# SHIELD1_1.net
KiCad netlist of a schematic drawn in EAGLE
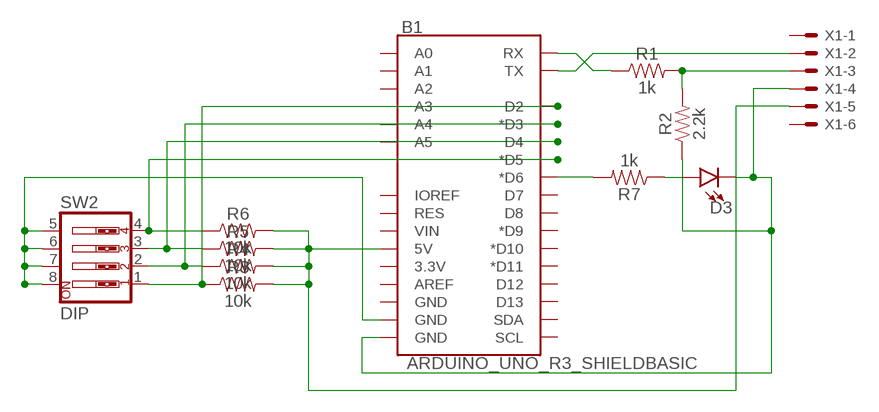
[diagram p0: schematic, sheet 1]

(export (version "E")
  (design (tool "Eeschema 10.0.6"))
  (components
    (comp (ref "B1")
      (value "ARDUINO_UNO_R3_SHIELDBASIC")
      (footprint "eagle-import:UNO_R3_SHIELD")
      (libsource (lib "eagle-import") (part "ARDUINO_UNO_R3_SHIELDBASIC"))
    )
    (comp (ref "D3")
      (value "LED5MM")
      (footprint "eagle-import:LED_5MM")
      (libsource (lib "eagle-import") (part "LED5MM"))
    )
    (comp (ref "R1")
      (value "1k")
      (footprint "eagle-import:AXIAL-0.3")
      (libsource (lib "eagle-import") (part "1KOHM-HORIZ-1/4W-1%"))
    )
    (comp (ref "R2")
      (value "2.2k")
      (footprint "eagle-import:AXIAL-0.3")
      (libsource (lib "eagle-import") (part "1KOHM-HORIZ-1/4W-1%"))
    )
    (comp (ref "R3")
      (value "10k")
      (footprint "eagle-import:AXIAL-0.3")
      (libsource (lib "eagle-import") (part "10KOHM-HORIZ-1/4W-1%"))
    )
    (comp (ref "R4")
      (value "10k")
      (footprint "eagle-import:AXIAL-0.3")
      (libsource (lib "eagle-import") (part "10KOHM-HORIZ-1/4W-1%"))
    )
    (comp (ref "R5")
      (value "10k")
      (footprint "eagle-import:AXIAL-0.3")
      (libsource (lib "eagle-import") (part "10KOHM-HORIZ-1/4W-1%"))
    )
    (comp (ref "R6")
      (value "10k")
      (footprint "eagle-import:AXIAL-0.3")
      (libsource (lib "eagle-import") (part "10KOHM-HORIZ-1/4W-1%"))
    )
    (comp (ref "R7")
      (value "1k")
      (footprint "eagle-import:AXIAL-0.3")
      (libsource (lib "eagle-import") (part "1KOHM-HORIZ-1/4W-1%"))
    )
    (comp (ref "SW2")
      (value "DIP")
      (footprint "eagle-import:EDG-04")
      (libsource (lib "eagle-import") (part "SW_DIP-4"))
    )
    (comp (ref "X1")
      (value "22-23-2061")
      (footprint "eagle-import:22-23-2061")
      (fields (field (name "MF") "MOLEX"))
      (libsource (lib "eagle-import") (part "22-23-2061"))
    )
  )
  (nets
    (net (code "1") (name "Net-(B1-*D3)") (class "Default")
      (node (ref "B1") (pin "D3") (pinfunction "*D3_D3") (pintype "bidirectional"))
      (node (ref "R4") (pin "P$1") (pinfunction "1_P$1") (pintype "passive"))
      (node (ref "SW2") (pin "2") (pinfunction "2_2") (pintype "passive"))
    )
    (net (code "2") (name "Net-(B1-*D5)") (class "Default")
      (node (ref "B1") (pin "D5") (pinfunction "*D5_D5") (pintype "bidirectional"))
      (node (ref "R6") (pin "P$1") (pinfunction "1_P$1") (pintype "passive"))
      (node (ref "SW2") (pin "4") (pinfunction "4_4") (pintype "passive"))
    )
    (net (code "3") (name "Net-(B1-*D6)") (class "Default")
      (node (ref "B1") (pin "D6") (pinfunction "*D6_D6") (pintype "bidirectional"))
      (node (ref "R7") (pin "P$2") (pinfunction "2_P$2") (pintype "passive"))
    )
    (net (code "4") (name "Net-(B1-GND-PadGND@1)") (class "Default")
      (node (ref "B1") (pin "GND@1") (pinfunction "GND_GND@1") (pintype "bidirectional"))
      (node (ref "SW2") (pin "5") (pinfunction "5_5") (pintype "passive"))
      (node (ref "SW2") (pin "6") (pinfunction "6_6") (pintype "passive"))
      (node (ref "SW2") (pin "7") (pinfunction "7_7") (pintype "passive"))
      (node (ref "SW2") (pin "8") (pinfunction "8_8") (pintype "passive"))
    )
    (net (code "5") (name "Net-(D3-C)") (class "Default")
      (node (ref "B1") (pin "GND@0") (pinfunction "GND_GND@0") (pintype "bidirectional"))
      (node (ref "D3") (pin "K") (pinfunction "C_K") (pintype "passive"))
      (node (ref "R2") (pin "P$1") (pinfunction "1_P$1") (pintype "passive"))
      (node (ref "X1") (pin "4") (pinfunction "S_4") (pintype "passive"))
    )
    (net (code "6") (name "Net-(R1-1)") (class "Default")
      (node (ref "B1") (pin "RX") (pinfunction "RX_RX") (pintype "bidirectional"))
      (node (ref "R1") (pin "P$1") (pinfunction "1_P$1") (pintype "passive"))
    )
    (net (code "7") (name "Net-(R1-2)") (class "Default")
      (node (ref "R1") (pin "P$2") (pinfunction "2_P$2") (pintype "passive"))
      (node (ref "R2") (pin "P$2") (pinfunction "2_P$2") (pintype "passive"))
      (node (ref "X1") (pin "3") (pinfunction "S_3") (pintype "passive"))
    )
    (net (code "8") (name "Net-(R3-1)") (class "Default")
      (node (ref "B1") (pin "D2") (pinfunction "D2_D2") (pintype "bidirectional"))
      (node (ref "R3") (pin "P$1") (pinfunction "1_P$1") (pintype "passive"))
      (node (ref "SW2") (pin "1") (pinfunction "1_1") (pintype "passive"))
    )
    (net (code "9") (name "Net-(R3-2)") (class "Default")
      (node (ref "B1") (pin "5V") (pinfunction "5V_5V") (pintype "bidirectional"))
      (node (ref "R3") (pin "P$2") (pinfunction "2_P$2") (pintype "passive"))
      (node (ref "R4") (pin "P$2") (pinfunction "2_P$2") (pintype "passive"))
      (node (ref "R5") (pin "P$2") (pinfunction "2_P$2") (pintype "passive"))
      (node (ref "R6") (pin "P$2") (pinfunction "2_P$2") (pintype "passive"))
      (node (ref "X1") (pin "5") (pinfunction "S_5") (pintype "passive"))
    )
    (net (code "10") (name "Net-(R5-1)") (class "Default")
      (node (ref "B1") (pin "D4") (pinfunction "D4_D4") (pintype "bidirectional"))
      (node (ref "R5") (pin "P$1") (pinfunction "1_P$1") (pintype "passive"))
      (node (ref "SW2") (pin "3") (pinfunction "3_3") (pintype "passive"))
    )
    (net (code "11") (name "Net-(R7-1)") (class "Default")
      (node (ref "D3") (pin "A") (pinfunction "A_A") (pintype "passive"))
      (node (ref "R7") (pin "P$1") (pinfunction "1_P$1") (pintype "passive"))
    )
    (net (code "12") (name "Net-(X1B-S)") (class "Default")
      (node (ref "B1") (pin "TX") (pinfunction "TX_TX") (pintype "bidirectional"))
      (node (ref "X1") (pin "2") (pinfunction "S_2") (pintype "passive"))
    )
    (net (code "13") (name "unconnected-(B1-*D9-PadD9)") (class "Default")
      (node (ref "B1") (pin "D9") (pinfunction "*D9_D9") (pintype "bidirectional"))
    )
    (net (code "14") (name "unconnected-(B1-*D10-PadD10)") (class "Default")
      (node (ref "B1") (pin "D10") (pinfunction "*D10_D10") (pintype "bidirectional"))
    )
    (net (code "15") (name "unconnected-(B1-*D11-PadD11)") (class "Default")
      (node (ref "B1") (pin "D11") (pinfunction "*D11_D11") (pintype "bidirectional"))
    )
    (net (code "16") (name "unconnected-(B1-GND-PadGND@2)") (class "Default")
      (node (ref "B1") (pin "GND@2") (pinfunction "GND_GND@2") (pintype "bidirectional"))
    )
    (net (code "17") (name "unconnected-(B1-Pad3.3V)") (class "Default")
      (node (ref "B1") (pin "3.3V") (pinfunction "3.3V_3.3V") (pintype "bidirectional"))
    )
    (net (code "18") (name "unconnected-(B1-PadA0)") (class "Default")
      (node (ref "B1") (pin "A0") (pinfunction "A0_A0") (pintype "bidirectional"))
    )
    (net (code "19") (name "unconnected-(B1-PadA1)") (class "Default")
      (node (ref "B1") (pin "A1") (pinfunction "A1_A1") (pintype "bidirectional"))
    )
    (net (code "20") (name "unconnected-(B1-PadA2)") (class "Default")
      (node (ref "B1") (pin "A2") (pinfunction "A2_A2") (pintype "bidirectional"))
    )
    (net (code "21") (name "unconnected-(B1-PadA3)") (class "Default")
      (node (ref "B1") (pin "A3") (pinfunction "A3_A3") (pintype "bidirectional"))
    )
    (net (code "22") (name "unconnected-(B1-PadA4)") (class "Default")
      (node (ref "B1") (pin "A4") (pinfunction "A4_A4") (pintype "bidirectional"))
    )
    (net (code "23") (name "unconnected-(B1-PadA5)") (class "Default")
      (node (ref "B1") (pin "A5") (pinfunction "A5_A5") (pintype "bidirectional"))
    )
    (net (code "24") (name "unconnected-(B1-PadAREF)") (class "Default")
      (node (ref "B1") (pin "AREF") (pinfunction "AREF_AREF") (pintype "bidirectional"))
    )
    (net (code "25") (name "unconnected-(B1-PadD7)") (class "Default")
      (node (ref "B1") (pin "D7") (pinfunction "D7_D7") (pintype "bidirectional"))
    )
    (net (code "26") (name "unconnected-(B1-PadD8)") (class "Default")
      (node (ref "B1") (pin "D8") (pinfunction "D8_D8") (pintype "bidirectional"))
    )
    (net (code "27") (name "unconnected-(B1-PadD12)") (class "Default")
      (node (ref "B1") (pin "D12") (pinfunction "D12_D12") (pintype "bidirectional"))
    )
    (net (code "28") (name "unconnected-(B1-PadD13)") (class "Default")
      (node (ref "B1") (pin "D13") (pinfunction "D13_D13") (pintype "bidirectional"))
    )
    (net (code "29") (name "unconnected-(B1-PadIOREF)") (class "Default")
      (node (ref "B1") (pin "IOREF") (pinfunction "IOREF_IOREF") (pintype "bidirectional"))
    )
    (net (code "30") (name "unconnected-(B1-PadRES)") (class "Default")
      (node (ref "B1") (pin "RES") (pinfunction "RES_RES") (pintype "bidirectional"))
    )
    (net (code "31") (name "unconnected-(B1-PadSCL)") (class "Default")
      (node (ref "B1") (pin "SCL") (pinfunction "SCL_SCL") (pintype "bidirectional"))
    )
    (net (code "32") (name "unconnected-(B1-PadSDA)") (class "Default")
      (node (ref "B1") (pin "SDA") (pinfunction "SDA_SDA") (pintype "bidirectional"))
    )
    (net (code "33") (name "unconnected-(B1-PadVIN)") (class "Default")
      (node (ref "B1") (pin "VIN") (pinfunction "VIN_VIN") (pintype "bidirectional"))
    )
    (net (code "34") (name "unconnected-(X1A-S-Pad1)") (class "Default")
      (node (ref "X1") (pin "1") (pinfunction "S_1") (pintype "passive"))
    )
    (net (code "35") (name "unconnected-(X1F-S-Pad6)") (class "Default")
      (node (ref "X1") (pin "6") (pinfunction "S_6") (pintype "passive"))
    )
  )
)
